# Microcontrolador.net
KiCad netlist of a schematic drawn in Altium Designer
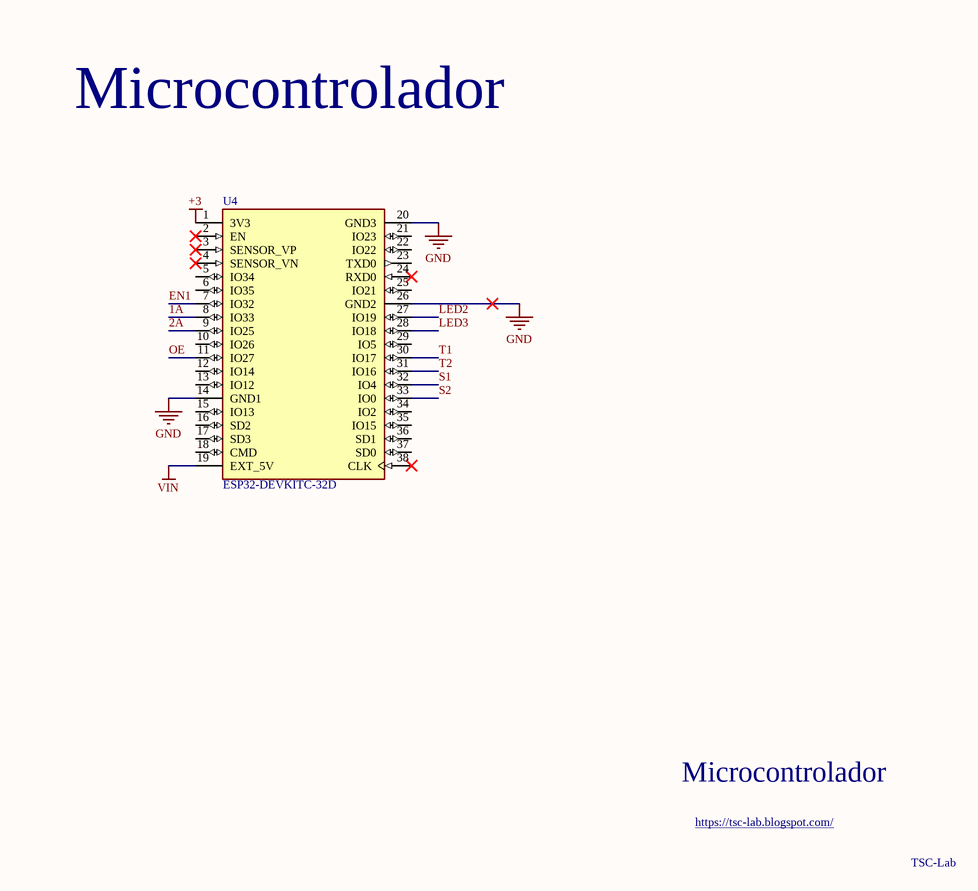
[diagram p0: Microcontrolador.SchDoc]

(export (version "E")
  (design (tool "Eeschema 10.0.6"))
  (components
    (comp (ref "U4")
      (value "ESP32-DEVKITC-32D")
      (footprint "MODULE_ESP32-DEVKITC-32D")
      (description "Eval Board For Esp-Wroom-32")
      (fields (field (name "MF") "{'manufacturer': u'Espressif Systems'}"))
      (libsource (lib "SnapEDA_Library") (part "ESP32-DEVKITC-32D"))
    )
  )
  (nets
    (net (code "1") (name "+3") (class "Default")
      (node (ref "U4") (pin "1") (pinfunction "3V3_1") (pintype "power_in"))
    )
    (net (code "2") (name "/1A") (class "Default")
      (node (ref "U4") (pin "8") (pinfunction "IO33_8") (pintype "bidirectional"))
    )
    (net (code "3") (name "/2A") (class "Default")
      (node (ref "U4") (pin "9") (pinfunction "IO25_9") (pintype "bidirectional"))
    )
    (net (code "4") (name "/EN1") (class "Default")
      (node (ref "U4") (pin "7") (pinfunction "IO32_7") (pintype "bidirectional"))
    )
    (net (code "5") (name "/LED2") (class "Default")
      (node (ref "U4") (pin "27") (pinfunction "IO19_27") (pintype "bidirectional"))
    )
    (net (code "6") (name "/LED3") (class "Default")
      (node (ref "U4") (pin "28") (pinfunction "IO18_28") (pintype "bidirectional"))
    )
    (net (code "7") (name "/OE") (class "Default")
      (node (ref "U4") (pin "11") (pinfunction "IO27_11") (pintype "bidirectional"))
    )
    (net (code "8") (name "/S1") (class "Default")
      (node (ref "U4") (pin "32") (pinfunction "IO4_32") (pintype "bidirectional"))
    )
    (net (code "9") (name "/S2") (class "Default")
      (node (ref "U4") (pin "33") (pinfunction "IO0_33") (pintype "bidirectional"))
    )
    (net (code "10") (name "/T1") (class "Default")
      (node (ref "U4") (pin "30") (pinfunction "IO17_30") (pintype "bidirectional"))
    )
    (net (code "11") (name "/T2") (class "Default")
      (node (ref "U4") (pin "31") (pinfunction "IO16_31") (pintype "bidirectional"))
    )
    (net (code "12") (name "GND") (class "Default")
      (node (ref "U4") (pin "14") (pinfunction "GND1_14") (pintype "power_in"))
      (node (ref "U4") (pin "20") (pinfunction "GND3_20") (pintype "power_in"))
      (node (ref "U4") (pin "26") (pinfunction "GND2_26") (pintype "power_in"))
    )
    (net (code "13") (name "VIN") (class "Default")
      (node (ref "U4") (pin "19") (pinfunction "EXT_5V_19") (pintype "power_in"))
    )
    (net (code "14") (name "unconnected-(U4-CLK-Pad38)") (class "Default")
      (node (ref "U4") (pin "38") (pinfunction "CLK_38") (pintype "input+no_connect"))
    )
    (net (code "15") (name "unconnected-(U4-CMD-Pad18)") (class "Default")
      (node (ref "U4") (pin "18") (pinfunction "CMD_18") (pintype "bidirectional"))
    )
    (net (code "16") (name "unconnected-(U4-EN-Pad2)") (class "Default")
      (node (ref "U4") (pin "2") (pinfunction "EN_2") (pintype "input+no_connect"))
    )
    (net (code "17") (name "unconnected-(U4-IO2-Pad34)") (class "Default")
      (node (ref "U4") (pin "34") (pinfunction "IO2_34") (pintype "bidirectional"))
    )
    (net (code "18") (name "unconnected-(U4-IO5-Pad29)") (class "Default")
      (node (ref "U4") (pin "29") (pinfunction "IO5_29") (pintype "bidirectional"))
    )
    (net (code "19") (name "unconnected-(U4-IO12-Pad13)") (class "Default")
      (node (ref "U4") (pin "13") (pinfunction "IO12_13") (pintype "bidirectional"))
    )
    (net (code "20") (name "unconnected-(U4-IO13-Pad15)") (class "Default")
      (node (ref "U4") (pin "15") (pinfunction "IO13_15") (pintype "bidirectional"))
    )
    (net (code "21") (name "unconnected-(U4-IO14-Pad12)") (class "Default")
      (node (ref "U4") (pin "12") (pinfunction "IO14_12") (pintype "bidirectional"))
    )
    (net (code "22") (name "unconnected-(U4-IO15-Pad35)") (class "Default")
      (node (ref "U4") (pin "35") (pinfunction "IO15_35") (pintype "bidirectional"))
    )
    (net (code "23") (name "unconnected-(U4-IO21-Pad25)") (class "Default")
      (node (ref "U4") (pin "25") (pinfunction "IO21_25") (pintype "bidirectional"))
    )
    (net (code "24") (name "unconnected-(U4-IO22-Pad22)") (class "Default")
      (node (ref "U4") (pin "22") (pinfunction "IO22_22") (pintype "bidirectional"))
    )
    (net (code "25") (name "unconnected-(U4-IO23-Pad21)") (class "Default")
      (node (ref "U4") (pin "21") (pinfunction "IO23_21") (pintype "bidirectional"))
    )
    (net (code "26") (name "unconnected-(U4-IO26-Pad10)") (class "Default")
      (node (ref "U4") (pin "10") (pinfunction "IO26_10") (pintype "bidirectional"))
    )
    (net (code "27") (name "unconnected-(U4-IO34-Pad5)") (class "Default")
      (node (ref "U4") (pin "5") (pinfunction "IO34_5") (pintype "bidirectional"))
    )
    (net (code "28") (name "unconnected-(U4-IO35-Pad6)") (class "Default")
      (node (ref "U4") (pin "6") (pinfunction "IO35_6") (pintype "bidirectional"))
    )
    (net (code "29") (name "unconnected-(U4-RXD0-Pad24)") (class "Default")
      (node (ref "U4") (pin "24") (pinfunction "RXD0_24") (pintype "input+no_connect"))
    )
    (net (code "30") (name "unconnected-(U4-SD0-Pad37)") (class "Default")
      (node (ref "U4") (pin "37") (pinfunction "SD0_37") (pintype "bidirectional"))
    )
    (net (code "31") (name "unconnected-(U4-SD1-Pad36)") (class "Default")
      (node (ref "U4") (pin "36") (pinfunction "SD1_36") (pintype "bidirectional"))
    )
    (net (code "32") (name "unconnected-(U4-SD2-Pad16)") (class "Default")
      (node (ref "U4") (pin "16") (pinfunction "SD2_16") (pintype "bidirectional"))
    )
    (net (code "33") (name "unconnected-(U4-SD3-Pad17)") (class "Default")
      (node (ref "U4") (pin "17") (pinfunction "SD3_17") (pintype "bidirectional"))
    )
    (net (code "34") (name "unconnected-(U4-SENSOR_VN-Pad4)") (class "Default")
      (node (ref "U4") (pin "4") (pinfunction "SENSOR_VN_4") (pintype "input+no_connect"))
    )
    (net (code "35") (name "unconnected-(U4-SENSOR_VP-Pad3)") (class "Default")
      (node (ref "U4") (pin "3") (pinfunction "SENSOR_VP_3") (pintype "input+no_connect"))
    )
    (net (code "36") (name "unconnected-(U4-TXD0-Pad23)") (class "Default")
      (node (ref "U4") (pin "23") (pinfunction "TXD0_23") (pintype "output"))
    )
  )
)
